# YOTSUBA_GNSS-coupler_ver_1_0.net
KiCad netlist of a schematic drawn in EAGLE
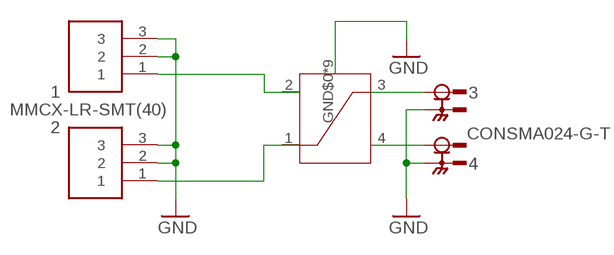
[diagram p0: schematic, sheet 1]

(export (version "E")
  (design (tool "Eeschema 10.0.6"))
  (components
    (comp (ref "1")
      (value "MMCX-LR-SMT(40)")
      (footprint "eagle-import:MMCX-LR-SMT(40)")
      (libsource (lib "eagle-import") (part "MMCX-LR-SMT(40)"))
    )
    (comp (ref "2")
      (value "MMCX-LR-SMT(40)")
      (footprint "eagle-import:MMCX-LR-SMT(40)")
      (libsource (lib "eagle-import") (part "MMCX-LR-SMT(40)"))
    )
    (comp (ref "3")
      (value "CONSMA024-G-T")
      (footprint "eagle-import:LINX_CONSMA024-G-T")
      (fields
        (field (name "DIGI-KEY_PART_NUMBER") "343-CONSMA024-G-TTR-ND")
        (field (name "MF") "Linx Technologies")
      )
      (libsource (lib "eagle-import") (part "CONSMA024-G-T"))
    )
    (comp (ref "4")
      (value "CONSMA024-G-T")
      (footprint "eagle-import:LINX_CONSMA024-G-T")
      (fields
        (field (name "DIGI-KEY_PART_NUMBER") "343-CONSMA024-G-TTR-ND")
        (field (name "MF") "Linx Technologies")
      )
      (libsource (lib "eagle-import") (part "CONSMA024-G-T"))
    )
    (comp (ref "U$3")
      (value "HC125.A")
      (footprint "eagle-import:HC125.A")
      (libsource (lib "eagle-import") (part "HC125.A"))
    )
  )
  (nets
    (net (code "1") (name "GND") (class "Default")
      (node (ref "1") (pin "2") (pinfunction "2_2") (pintype "bidirectional"))
      (node (ref "1") (pin "3") (pinfunction "3_3") (pintype "bidirectional"))
      (node (ref "2") (pin "2") (pinfunction "2_2") (pintype "bidirectional"))
      (node (ref "2") (pin "3") (pinfunction "3_3") (pintype "bidirectional"))
      (node (ref "3") (pin "G1") (pinfunction "2_G1") (pintype "passive"))
      (node (ref "3") (pin "G2") (pinfunction "2_G2") (pintype "passive"))
      (node (ref "4") (pin "G1") (pinfunction "2_G1") (pintype "passive"))
      (node (ref "4") (pin "G2") (pinfunction "2_G2") (pintype "passive"))
      (node (ref "U$3") (pin "GND$0") (pinfunction "GND_GND$0") (pintype "bidirectional"))
      (node (ref "U$3") (pin "GND$1") (pinfunction "GND_GND$1") (pintype "bidirectional"))
      (node (ref "U$3") (pin "GND$2") (pinfunction "GND_GND$2") (pintype "bidirectional"))
      (node (ref "U$3") (pin "GND$3") (pinfunction "GND_GND$3") (pintype "bidirectional"))
      (node (ref "U$3") (pin "GND$4") (pinfunction "GND_GND$4") (pintype "bidirectional"))
      (node (ref "U$3") (pin "GND$5") (pinfunction "GND_GND$5") (pintype "bidirectional"))
      (node (ref "U$3") (pin "GND$6") (pinfunction "GND_GND$6") (pintype "bidirectional"))
      (node (ref "U$3") (pin "GND$7") (pinfunction "GND_GND$7") (pintype "bidirectional"))
      (node (ref "U$3") (pin "GND$8") (pinfunction "GND_GND$8") (pintype "bidirectional"))
    )
    (net (code "2") (name "Net-(1-Pad1)") (class "Default")
      (node (ref "1") (pin "1") (pinfunction "1_1") (pintype "bidirectional"))
      (node (ref "U$3") (pin "2") (pinfunction "2_2") (pintype "bidirectional"))
    )
    (net (code "3") (name "Net-(2-Pad1)") (class "Default")
      (node (ref "2") (pin "1") (pinfunction "1_1") (pintype "bidirectional"))
      (node (ref "U$3") (pin "1") (pinfunction "1_1") (pintype "bidirectional"))
    )
    (net (code "4") (name "Net-(3-Pad1)") (class "Default")
      (node (ref "3") (pin "1") (pinfunction "1_1") (pintype "passive"))
      (node (ref "U$3") (pin "3") (pinfunction "3_3") (pintype "bidirectional"))
    )
    (net (code "5") (name "Net-(4-Pad1)") (class "Default")
      (node (ref "4") (pin "1") (pinfunction "1_1") (pintype "passive"))
      (node (ref "U$3") (pin "4") (pinfunction "4_4") (pintype "bidirectional"))
    )
  )
)
